# Ifargan_door_lock.net
KiCad netlist of a schematic drawn in EAGLE
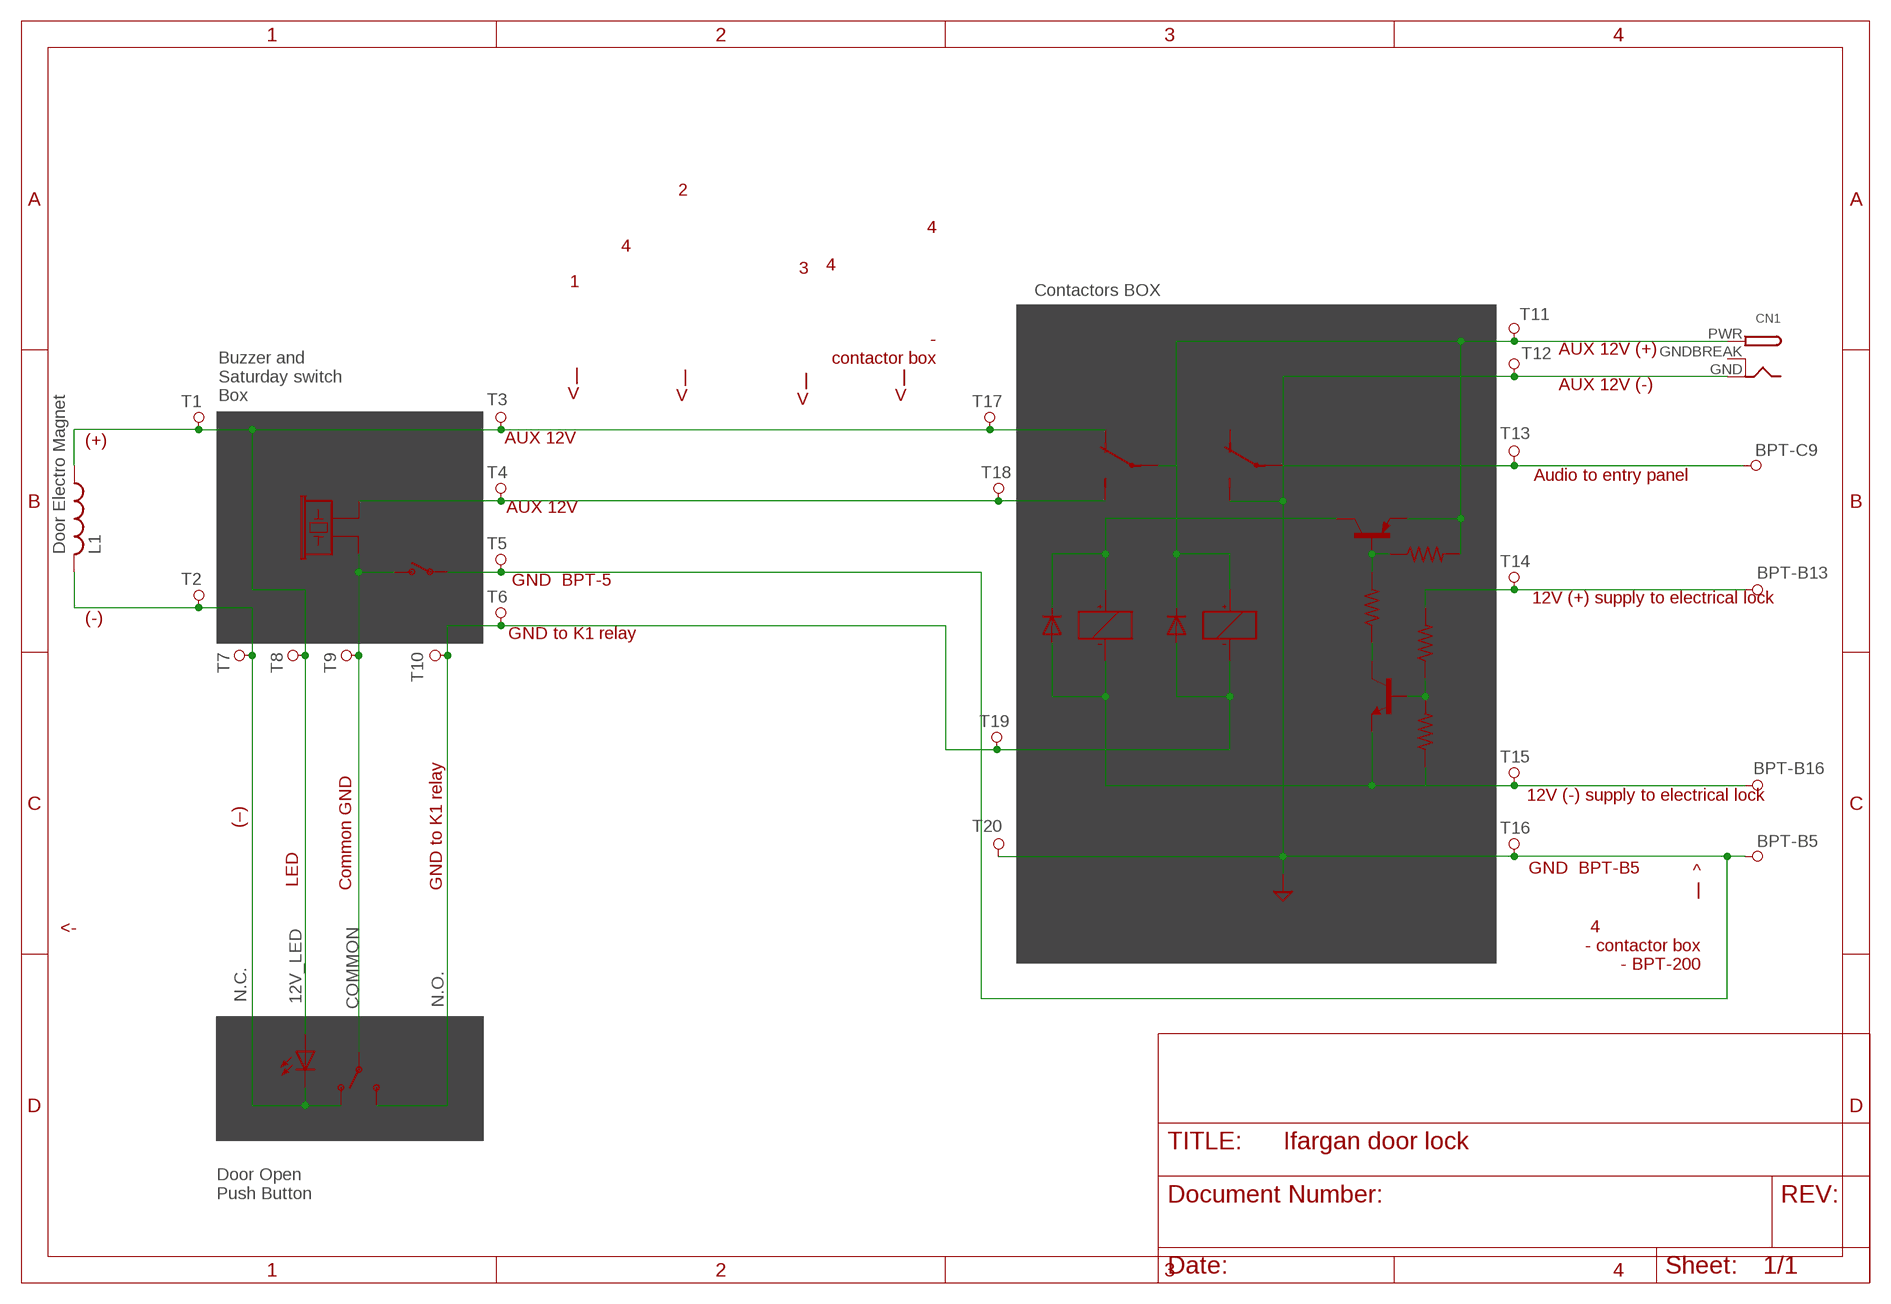
[diagram p0: schematic, sheet 1]

(export (version "E")
  (design (tool "Eeschema 10.0.6"))
  (components
    (comp (ref "BPT-B5")
      (value "PAD_TERMINAL-4.1MMROUND")
      (footprint "eagle-import:PAD_ROUND_4.1MM")
      (libsource (lib "eagle-import") (part "PAD_TERMINAL-4.1MMROUND"))
    )
    (comp (ref "BPT-B13")
      (value "PAD_TERMINAL-4.1MMROUND")
      (footprint "eagle-import:PAD_ROUND_4.1MM")
      (libsource (lib "eagle-import") (part "PAD_TERMINAL-4.1MMROUND"))
    )
    (comp (ref "BPT-B16")
      (value "PAD_TERMINAL-4.1MMROUND")
      (footprint "eagle-import:PAD_ROUND_4.1MM")
      (libsource (lib "eagle-import") (part "PAD_TERMINAL-4.1MMROUND"))
    )
    (comp (ref "BPT-C9")
      (value "PAD_TERMINAL-4.1MMROUND")
      (footprint "eagle-import:PAD_ROUND_4.1MM")
      (libsource (lib "eagle-import") (part "PAD_TERMINAL-4.1MMROUND"))
    )
    (comp (ref "CN1")
      (value "DCBARRELPTH")
      (footprint "eagle-import:DCJACK_2MM_PTH")
      (libsource (lib "eagle-import") (part "DCBARRELPTH"))
    )
    (comp (ref "D1")
      (value "1N4004")
      (footprint "eagle-import:DO41-10")
      (libsource (lib "eagle-import") (part "1N4004"))
    )
    (comp (ref "D2")
      (value "1N4004")
      (footprint "eagle-import:DO41-10")
      (libsource (lib "eagle-import") (part "1N4004"))
    )
    (comp (ref "K1")
      (value "Relay")
      (footprint "eagle-import:DS2Y")
      (fields (field (name "MPN") "DS2Y-S-DC1.5V"))
      (libsource (lib "eagle-import") (part "DS2Y-S-DC1.5V"))
    )
    (comp (ref "K2")
      (value "Relay")
      (footprint "eagle-import:DS2Y")
      (fields (field (name "MPN") "DS2Y-S-DC1.5V"))
      (libsource (lib "eagle-import") (part "DS2Y-S-DC1.5V"))
    )
    (comp (ref "L1")
      (value "Door Electro Magnet")
      (footprint "eagle-import:IRF-3")
      (libsource (lib "eagle-import") (part "L-USIRF-3"))
    )
    (comp (ref "LED1")
      (value "LED")
      (footprint "eagle-import:SMARTLED-TTW")
      (libsource (lib "eagle-import") (part "LED"))
    )
    (comp (ref "Q1")
      (value "2N2905")
      (footprint "eagle-import:TO5")
      (libsource (lib "eagle-import") (part "2N2905"))
    )
    (comp (ref "Q2")
      (value "2N2219")
      (footprint "eagle-import:TO5")
      (libsource (lib "eagle-import") (part "2N2219"))
    )
    (comp (ref "R1")
      (value "10K")
      (footprint "eagle-import:0207_15")
      (libsource (lib "eagle-import") (part "R-US_0207/15"))
    )
    (comp (ref "R2")
      (value "1K")
      (footprint "eagle-import:0207_15")
      (libsource (lib "eagle-import") (part "R-US_0207/15"))
    )
    (comp (ref "R3")
      (value "1K")
      (footprint "eagle-import:0207_15")
      (libsource (lib "eagle-import") (part "R-US_0207/15"))
    )
    (comp (ref "R4")
      (value "10K")
      (footprint "eagle-import:0207_15")
      (libsource (lib "eagle-import") (part "R-US_0207/15"))
    )
    (comp (ref "S1")
      (value "Door Open P.B.")
      (footprint "eagle-import:KPS-1290")
      (libsource (lib "eagle-import") (part "SWITCH_SPDT"))
    )
    (comp (ref "S2")
      (value "Saturday SW")
      (footprint "eagle-import:SPST_SMT_19192")
      (libsource (lib "eagle-import") (part "SWITCH_SPST"))
    )
    (comp (ref "SG1")
      (value "Buzzer")
      (footprint "eagle-import:F_EE21P")
      (libsource (lib "eagle-import") (part "F/EE21P"))
    )
    (comp (ref "T1")
      (value "PAD_TERMINAL-4.1MMROUND")
      (footprint "eagle-import:PAD_ROUND_4.1MM")
      (libsource (lib "eagle-import") (part "PAD_TERMINAL-4.1MMROUND"))
    )
    (comp (ref "T2")
      (value "PAD_TERMINAL-4.1MMROUND")
      (footprint "eagle-import:PAD_ROUND_4.1MM")
      (libsource (lib "eagle-import") (part "PAD_TERMINAL-4.1MMROUND"))
    )
    (comp (ref "T3")
      (value "PAD_TERMINAL-4.1MMROUND")
      (footprint "eagle-import:PAD_ROUND_4.1MM")
      (libsource (lib "eagle-import") (part "PAD_TERMINAL-4.1MMROUND"))
    )
    (comp (ref "T4")
      (value "PAD_TERMINAL-4.1MMROUND")
      (footprint "eagle-import:PAD_ROUND_4.1MM")
      (libsource (lib "eagle-import") (part "PAD_TERMINAL-4.1MMROUND"))
    )
    (comp (ref "T5")
      (value "PAD_TERMINAL-4.1MMROUND")
      (footprint "eagle-import:PAD_ROUND_4.1MM")
      (libsource (lib "eagle-import") (part "PAD_TERMINAL-4.1MMROUND"))
    )
    (comp (ref "T6")
      (value "PAD_TERMINAL-4.1MMROUND")
      (footprint "eagle-import:PAD_ROUND_4.1MM")
      (libsource (lib "eagle-import") (part "PAD_TERMINAL-4.1MMROUND"))
    )
    (comp (ref "T7")
      (value "PAD_TERMINAL-4.1MMROUND")
      (footprint "eagle-import:PAD_ROUND_4.1MM")
      (libsource (lib "eagle-import") (part "PAD_TERMINAL-4.1MMROUND"))
    )
    (comp (ref "T8")
      (value "PAD_TERMINAL-4.1MMROUND")
      (footprint "eagle-import:PAD_ROUND_4.1MM")
      (libsource (lib "eagle-import") (part "PAD_TERMINAL-4.1MMROUND"))
    )
    (comp (ref "T9")
      (value "PAD_TERMINAL-4.1MMROUND")
      (footprint "eagle-import:PAD_ROUND_4.1MM")
      (libsource (lib "eagle-import") (part "PAD_TERMINAL-4.1MMROUND"))
    )
    (comp (ref "T10")
      (value "PAD_TERMINAL-4.1MMROUND")
      (footprint "eagle-import:PAD_ROUND_4.1MM")
      (libsource (lib "eagle-import") (part "PAD_TERMINAL-4.1MMROUND"))
    )
    (comp (ref "T11")
      (value "PAD_TERMINAL-4.1MMROUND")
      (footprint "eagle-import:PAD_ROUND_4.1MM")
      (libsource (lib "eagle-import") (part "PAD_TERMINAL-4.1MMROUND"))
    )
    (comp (ref "T12")
      (value "PAD_TERMINAL-4.1MMROUND")
      (footprint "eagle-import:PAD_ROUND_4.1MM")
      (libsource (lib "eagle-import") (part "PAD_TERMINAL-4.1MMROUND"))
    )
    (comp (ref "T13")
      (value "PAD_TERMINAL-4.1MMROUND")
      (footprint "eagle-import:PAD_ROUND_4.1MM")
      (libsource (lib "eagle-import") (part "PAD_TERMINAL-4.1MMROUND"))
    )
    (comp (ref "T14")
      (value "PAD_TERMINAL-4.1MMROUND")
      (footprint "eagle-import:PAD_ROUND_4.1MM")
      (libsource (lib "eagle-import") (part "PAD_TERMINAL-4.1MMROUND"))
    )
    (comp (ref "T15")
      (value "PAD_TERMINAL-4.1MMROUND")
      (footprint "eagle-import:PAD_ROUND_4.1MM")
      (libsource (lib "eagle-import") (part "PAD_TERMINAL-4.1MMROUND"))
    )
    (comp (ref "T16")
      (value "PAD_TERMINAL-4.1MMROUND")
      (footprint "eagle-import:PAD_ROUND_4.1MM")
      (libsource (lib "eagle-import") (part "PAD_TERMINAL-4.1MMROUND"))
    )
    (comp (ref "T17")
      (value "PAD_TERMINAL-4.1MMROUND")
      (footprint "eagle-import:PAD_ROUND_4.1MM")
      (libsource (lib "eagle-import") (part "PAD_TERMINAL-4.1MMROUND"))
    )
    (comp (ref "T18")
      (value "PAD_TERMINAL-4.1MMROUND")
      (footprint "eagle-import:PAD_ROUND_4.1MM")
      (libsource (lib "eagle-import") (part "PAD_TERMINAL-4.1MMROUND"))
    )
    (comp (ref "T19")
      (value "PAD_TERMINAL-4.1MMROUND")
      (footprint "eagle-import:PAD_ROUND_4.1MM")
      (libsource (lib "eagle-import") (part "PAD_TERMINAL-4.1MMROUND"))
    )
    (comp (ref "T20")
      (value "PAD_TERMINAL-4.1MMROUND")
      (footprint "eagle-import:PAD_ROUND_4.1MM")
      (libsource (lib "eagle-import") (part "PAD_TERMINAL-4.1MMROUND"))
    )
  )
  (nets
    (net (code "1") (name "/12V_LED") (class "Default")
      (node (ref "K2") (pin "6") (pinfunction "O_6") (pintype "passive"))
      (node (ref "L1") (pin "1") (pinfunction "1_1") (pintype "passive"))
      (node (ref "LED1") (pin "A@1") (pinfunction "A_A@1") (pintype "passive"))
      (node (ref "T1") (pin "P") (pinfunction "P_P") (pintype "passive"))
      (node (ref "T17") (pin "P") (pinfunction "P_P") (pintype "passive"))
      (node (ref "T3") (pin "P") (pinfunction "P_P") (pintype "passive"))
      (node (ref "T8") (pin "P") (pinfunction "P_P") (pintype "passive"))
    )
    (net (code "2") (name "/AUX-12V") (class "Default")
      (node (ref "CN1") (pin "PWR") (pinfunction "PWR_PWR") (pintype "power_in"))
      (node (ref "D2") (pin "C") (pinfunction "C_C") (pintype "passive"))
      (node (ref "K1") (pin "1") (pinfunction "+_1") (pintype "passive"))
      (node (ref "K2") (pin "4") (pinfunction "P_4") (pintype "passive"))
      (node (ref "Q1") (pin "1") (pinfunction "E_1") (pintype "passive"))
      (node (ref "R1") (pin "2") (pinfunction "2_2") (pintype "passive"))
      (node (ref "T11") (pin "P") (pinfunction "P_P") (pintype "passive"))
    )
    (net (code "3") (name "/COMMON") (class "Default")
      (node (ref "S1") (pin "P") (pinfunction "P_P") (pintype "passive"))
      (node (ref "S2") (pin "C") (pinfunction "S_C") (pintype "passive"))
      (node (ref "SG1") (pin "1") (pinfunction "1_1") (pintype "passive"))
      (node (ref "T9") (pin "P") (pinfunction "P_P") (pintype "passive"))
    )
    (net (code "4") (name "/GNDBREAK") (class "Default")
      (node (ref "CN1") (pin "GNDBREAK") (pinfunction "GNDBREAK_GNDBREAK") (pintype "power_in"))
    )
    (net (code "5") (name "/N.C.") (class "Default")
      (node (ref "L1") (pin "2") (pinfunction "2_2") (pintype "passive"))
      (node (ref "LED1") (pin "C@1") (pinfunction "C_C@1") (pintype "passive"))
      (node (ref "S1") (pin "O") (pinfunction "O_O") (pintype "passive"))
      (node (ref "T2") (pin "P") (pinfunction "P_P") (pintype "passive"))
      (node (ref "T7") (pin "P") (pinfunction "P_P") (pintype "passive"))
    )
    (net (code "6") (name "/N.O.") (class "Default")
      (node (ref "D2") (pin "A") (pinfunction "A_A") (pintype "passive"))
      (node (ref "K1") (pin "16") (pinfunction "-_16") (pintype "passive"))
      (node (ref "S1") (pin "S") (pinfunction "S_S") (pintype "passive"))
      (node (ref "T10") (pin "P") (pinfunction "P_P") (pintype "passive"))
      (node (ref "T19") (pin "P") (pinfunction "P_P") (pintype "passive"))
      (node (ref "T6") (pin "P") (pinfunction "P_P") (pintype "passive"))
    )
    (net (code "7") (name "GND") (class "Default")
      (node (ref "BPT-B5") (pin "P") (pinfunction "P_P") (pintype "passive"))
      (node (ref "CN1") (pin "GND") (pinfunction "GND_GND") (pintype "power_in"))
      (node (ref "K1") (pin "8") (pinfunction "S_8") (pintype "passive"))
      (node (ref "S2") (pin "B") (pinfunction "P_B") (pintype "passive"))
      (node (ref "T12") (pin "P") (pinfunction "P_P") (pintype "passive"))
      (node (ref "T16") (pin "P") (pinfunction "P_P") (pintype "passive"))
      (node (ref "T20") (pin "P") (pinfunction "P_P") (pintype "passive"))
      (node (ref "T5") (pin "P") (pinfunction "P_P") (pintype "passive"))
    )
    (net (code "8") (name "Net-(BPT-B13-PadP)") (class "Default")
      (node (ref "BPT-B13") (pin "P") (pinfunction "P_P") (pintype "passive"))
      (node (ref "R3") (pin "2") (pinfunction "2_2") (pintype "passive"))
      (node (ref "T14") (pin "P") (pinfunction "P_P") (pintype "passive"))
    )
    (net (code "9") (name "Net-(K1B-P)") (class "Default")
      (node (ref "BPT-C9") (pin "P") (pinfunction "P_P") (pintype "passive"))
      (node (ref "K1") (pin "4") (pinfunction "P_4") (pintype "passive"))
    )
    (net (code "10") (name "Net-(K2A-+)") (class "Default")
      (node (ref "D1") (pin "C") (pinfunction "C_C") (pintype "passive"))
      (node (ref "K2") (pin "1") (pinfunction "+_1") (pintype "passive"))
      (node (ref "Q1") (pin "3") (pinfunction "C_3") (pintype "passive"))
    )
    (net (code "11") (name "Net-(K2A--)") (class "Default")
      (node (ref "BPT-B16") (pin "P") (pinfunction "P_P") (pintype "passive"))
      (node (ref "D1") (pin "A") (pinfunction "A_A") (pintype "passive"))
      (node (ref "K2") (pin "16") (pinfunction "-_16") (pintype "passive"))
      (node (ref "Q2") (pin "1") (pinfunction "E_1") (pintype "passive"))
      (node (ref "R4") (pin "1") (pinfunction "1_1") (pintype "passive"))
      (node (ref "T15") (pin "P") (pinfunction "P_P") (pintype "passive"))
    )
    (net (code "12") (name "Net-(K2B-S)") (class "Default")
      (node (ref "K2") (pin "8") (pinfunction "S_8") (pintype "passive"))
      (node (ref "SG1") (pin "2") (pinfunction "2_2") (pintype "passive"))
      (node (ref "T18") (pin "P") (pinfunction "P_P") (pintype "passive"))
      (node (ref "T4") (pin "P") (pinfunction "P_P") (pintype "passive"))
    )
    (net (code "13") (name "Net-(Q1-B)") (class "Default")
      (node (ref "Q1") (pin "2") (pinfunction "B_2") (pintype "passive"))
      (node (ref "R1") (pin "1") (pinfunction "1_1") (pintype "passive"))
      (node (ref "R2") (pin "2") (pinfunction "2_2") (pintype "passive"))
    )
    (net (code "14") (name "Net-(Q2-B)") (class "Default")
      (node (ref "Q2") (pin "2") (pinfunction "B_2") (pintype "passive"))
      (node (ref "R3") (pin "1") (pinfunction "1_1") (pintype "passive"))
      (node (ref "R4") (pin "2") (pinfunction "2_2") (pintype "passive"))
    )
    (net (code "15") (name "Net-(Q2-C)") (class "Default")
      (node (ref "Q2") (pin "3") (pinfunction "C_3") (pintype "passive"))
      (node (ref "R2") (pin "1") (pinfunction "1_1") (pintype "passive"))
    )
    (net (code "16") (name "unconnected-(K1B-O-Pad6)") (class "Default")
      (node (ref "K1") (pin "6") (pinfunction "O_6") (pintype "passive"))
    )
    (net (code "17") (name "unconnected-(T13-PadP)") (class "Default")
      (node (ref "T13") (pin "P") (pinfunction "P_P") (pintype "passive"))
    )
  )
)
